# GYRO_3-AXIS_-_ITG-3200.net
KiCad netlist of a schematic drawn in Altium Designer
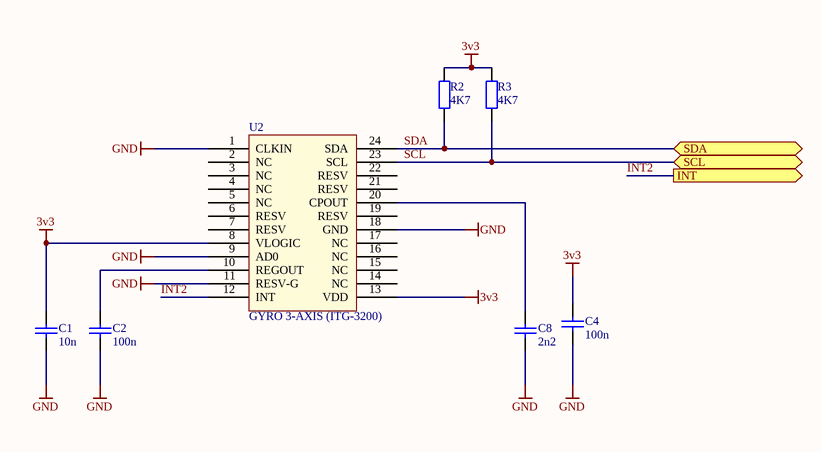
[diagram p0: GYRO 3-AXIS - ITG-3200.SchDoc]

(export (version "E")
  (design (tool "Eeschema 10.0.6"))
  (components
    (comp (ref "C1")
      (value "10n")
      (footprint "C0805")
      (fields (field (name "TOLERANCE") "0.1") (field (name "AUTHOR") "Willy Pietersz"))
      (libsource (lib "OurDb") (part "cap_NonPolar"))
    )
    (comp (ref "C2")
      (value "100n")
      (footprint "C0805")
      (fields (field (name "TOLERANCE") "0.1") (field (name "AUTHOR") "Willy Pietersz"))
      (libsource (lib "OurDb") (part "cap_NonPolar"))
    )
    (comp (ref "C4")
      (value "100n")
      (footprint "C0805")
      (fields (field (name "TOLERANCE") "0.1") (field (name "AUTHOR") "Willy Pietersz"))
      (libsource (lib "OurDb") (part "cap_NonPolar"))
    )
    (comp (ref "C8")
      (value "2n2")
      (footprint "C0805")
      (fields (field (name "TOLERANCE") "0.1") (field (name "AUTHOR") "Willy Pietersz"))
      (libsource (lib "OurDb") (part "cap_NonPolar"))
    )
    (comp (ref "R2")
      (value "4K7")
      (footprint "R0805")
      (description "Resistor")
      (fields
        (field (name "POWER") "0.25W")
        (field (name "TOLERANCE") "0.05")
        (field (name "PUBLISHER") "Altium Limited")
        (field (name "AUTHOR") "Willy Pietersz")
      )
      (libsource (lib "OurDb") (part "RESISTOR"))
    )
    (comp (ref "R3")
      (value "4K7")
      (footprint "R0805")
      (description "Resistor")
      (fields
        (field (name "POWER") "0.25W")
        (field (name "TOLERANCE") "0.05")
        (field (name "PUBLISHER") "Altium Limited")
        (field (name "AUTHOR") "Willy Pietersz")
      )
      (libsource (lib "OurDb") (part "RESISTOR"))
    )
    (comp (ref "U2")
      (value "GYRO 3-AXIS (ITG-3200)")
      (footprint "QFN50P400X400-24V2M - GYRO 3axis")
      (description "Gyro, 3-axis")
      (fields (field (name "PART NUMBER") "ITG-3200"))
      (libsource (lib "OurDb") (part "ITG-3200"))
    )
  )
  (nets
    (net (code "1") (name "/INT2") (class "Default")
      (node (ref "U2") (pin "12") (pinfunction "INT_12") (pintype "passive"))
    )
    (net (code "2") (name "/SCL") (class "Default")
      (node (ref "R3") (pin "2") (pinfunction "2_2") (pintype "passive"))
      (node (ref "U2") (pin "23") (pinfunction "SCL_23") (pintype "passive"))
    )
    (net (code "3") (name "/SDA") (class "Default")
      (node (ref "R2") (pin "2") (pinfunction "2_2") (pintype "passive"))
      (node (ref "U2") (pin "24") (pinfunction "SDA_24") (pintype "passive"))
    )
    (net (code "4") (name "3v3") (class "Default")
      (node (ref "C1") (pin "2") (pinfunction "2_2") (pintype "passive"))
      (node (ref "C4") (pin "2") (pinfunction "2_2") (pintype "passive"))
      (node (ref "R2") (pin "1") (pinfunction "1_1") (pintype "passive"))
      (node (ref "R3") (pin "1") (pinfunction "1_1") (pintype "passive"))
      (node (ref "U2") (pin "13") (pinfunction "VDD_13") (pintype "passive"))
      (node (ref "U2") (pin "8") (pinfunction "VLOGIC_8") (pintype "passive"))
    )
    (net (code "5") (name "GND") (class "Default")
      (node (ref "C1") (pin "1") (pinfunction "1_1") (pintype "passive"))
      (node (ref "C2") (pin "1") (pinfunction "1_1") (pintype "passive"))
      (node (ref "C4") (pin "1") (pinfunction "1_1") (pintype "passive"))
      (node (ref "C8") (pin "1") (pinfunction "1_1") (pintype "passive"))
      (node (ref "U2") (pin "1") (pinfunction "CLKIN_1") (pintype "passive"))
      (node (ref "U2") (pin "11") (pinfunction "RESV-G_11") (pintype "passive"))
      (node (ref "U2") (pin "18") (pinfunction "GND_18") (pintype "passive"))
      (node (ref "U2") (pin "9") (pinfunction "AD0_9") (pintype "passive"))
    )
    (net (code "6") (name "Net-(U2-CPOUT)") (class "Default")
      (node (ref "C8") (pin "2") (pinfunction "2_2") (pintype "passive"))
      (node (ref "U2") (pin "20") (pinfunction "CPOUT_20") (pintype "passive"))
    )
    (net (code "7") (name "Net-(U2-REGOUT)") (class "Default")
      (node (ref "C2") (pin "2") (pinfunction "2_2") (pintype "passive"))
      (node (ref "U2") (pin "10") (pinfunction "REGOUT_10") (pintype "passive"))
    )
    (net (code "8") (name "unconnected-(U2-NC-Pad2)") (class "Default")
      (node (ref "U2") (pin "2") (pinfunction "NC_2") (pintype "passive"))
    )
    (net (code "9") (name "unconnected-(U2-NC-Pad3)") (class "Default")
      (node (ref "U2") (pin "3") (pinfunction "NC_3") (pintype "passive"))
    )
    (net (code "10") (name "unconnected-(U2-NC-Pad4)") (class "Default")
      (node (ref "U2") (pin "4") (pinfunction "NC_4") (pintype "passive"))
    )
    (net (code "11") (name "unconnected-(U2-NC-Pad5)") (class "Default")
      (node (ref "U2") (pin "5") (pinfunction "NC_5") (pintype "passive"))
    )
    (net (code "12") (name "unconnected-(U2-NC-Pad14)") (class "Default")
      (node (ref "U2") (pin "14") (pinfunction "NC_14") (pintype "passive"))
    )
    (net (code "13") (name "unconnected-(U2-NC-Pad15)") (class "Default")
      (node (ref "U2") (pin "15") (pinfunction "NC_15") (pintype "passive"))
    )
    (net (code "14") (name "unconnected-(U2-NC-Pad16)") (class "Default")
      (node (ref "U2") (pin "16") (pinfunction "NC_16") (pintype "passive"))
    )
    (net (code "15") (name "unconnected-(U2-NC-Pad17)") (class "Default")
      (node (ref "U2") (pin "17") (pinfunction "NC_17") (pintype "passive"))
    )
    (net (code "16") (name "unconnected-(U2-RESV-Pad6)") (class "Default")
      (node (ref "U2") (pin "6") (pinfunction "RESV_6") (pintype "passive"))
    )
    (net (code "17") (name "unconnected-(U2-RESV-Pad7)") (class "Default")
      (node (ref "U2") (pin "7") (pinfunction "RESV_7") (pintype "passive"))
    )
    (net (code "18") (name "unconnected-(U2-RESV-Pad19)") (class "Default")
      (node (ref "U2") (pin "19") (pinfunction "RESV_19") (pintype "passive"))
    )
    (net (code "19") (name "unconnected-(U2-RESV-Pad21)") (class "Default")
      (node (ref "U2") (pin "21") (pinfunction "RESV_21") (pintype "passive"))
    )
    (net (code "20") (name "unconnected-(U2-RESV-Pad22)") (class "Default")
      (node (ref "U2") (pin "22") (pinfunction "RESV_22") (pintype "passive"))
    )
  )
)
